# SDCARD.net
KiCad netlist of a schematic drawn in Altium Designer
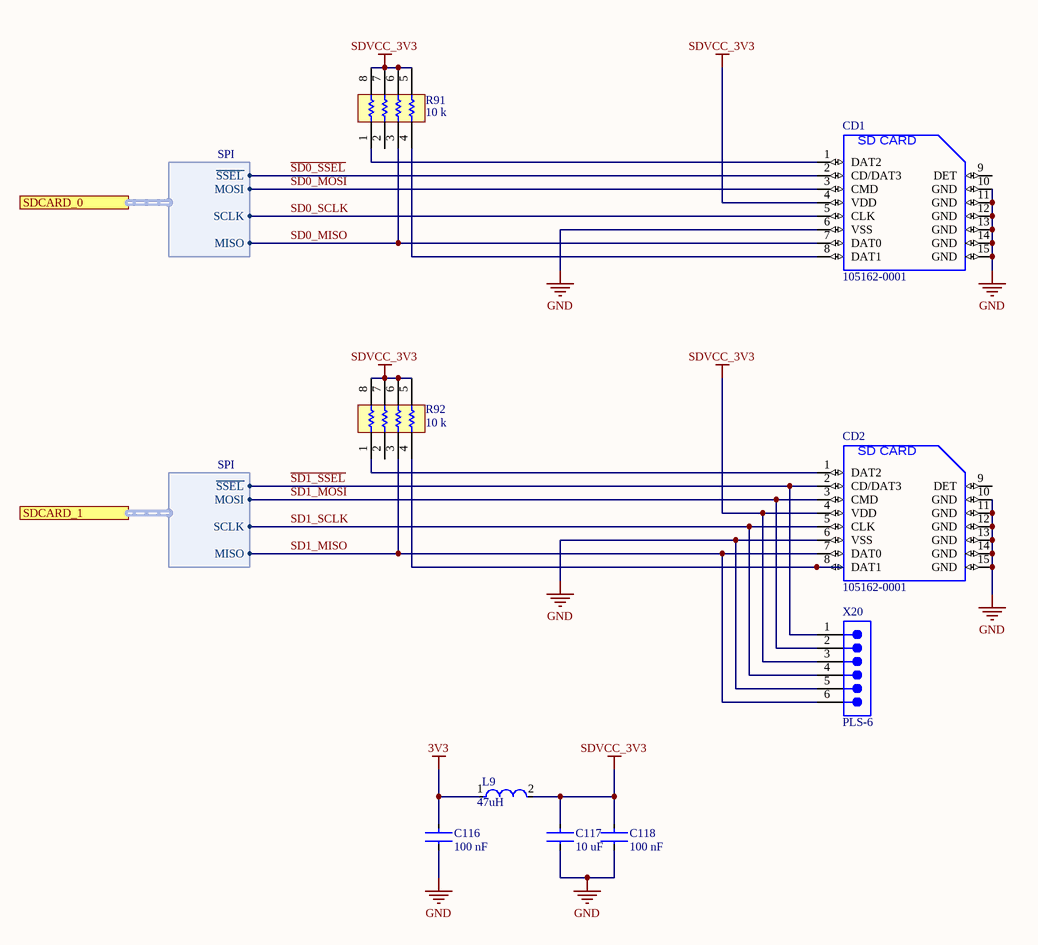
[diagram p0: SDCARD.SchDoc]

(export (version "E")
  (design (tool "Eeschema 10.0.6"))
  (components
    (comp (ref "C116")
      (value "CC0805-1.5pF")
      (footprint "CC0805")
      (description "CL21 Series 0805 1.5pF 50V ±0.25pF Tolerance C0G Multilayer Ceramic Chip Capacitor")
      (fields
        (field (name "MANUFACTURER PART NUMBER") "CL21C1R5CBANNNC")
        (field (name "MANUFACTURER") "Samsung")
        (field (name "CAPACITANCE") "100 nF")
      )
      (libsource (lib "zxevo") (part "CC0805"))
    )
    (comp (ref "C117")
      (value "CC0805-1.5pF")
      (footprint "CC0805")
      (description "CL21 Series 0805 1.5pF 50V ±0.25pF Tolerance C0G Multilayer Ceramic Chip Capacitor")
      (fields
        (field (name "MANUFACTURER PART NUMBER") "CL21C1R5CBANNNC")
        (field (name "MANUFACTURER") "Samsung")
        (field (name "CAPACITANCE") "10 uF")
      )
      (libsource (lib "zxevo") (part "CC0805"))
    )
    (comp (ref "C118")
      (value "CC0805-1.5pF")
      (footprint "CC0805")
      (description "CL21 Series 0805 1.5pF 50V ±0.25pF Tolerance C0G Multilayer Ceramic Chip Capacitor")
      (fields
        (field (name "MANUFACTURER PART NUMBER") "CL21C1R5CBANNNC")
        (field (name "MANUFACTURER") "Samsung")
        (field (name "CAPACITANCE") "100 nF")
      )
      (libsource (lib "zxevo") (part "CC0805"))
    )
    (comp (ref "CD1")
      (value "105162-0001")
      (footprint "105162-0001")
      (description "9 (8 + 1) Position Card Connector microSDâ„¢ Surface Mount, Right Angle Gold")
      (fields (field (name "MF") "Molex"))
      (libsource (lib "zxevo") (part "105162-0001"))
    )
    (comp (ref "CD2")
      (value "105162-0001")
      (footprint "105162-0001")
      (description "9 (8 + 1) Position Card Connector microSDâ„¢ Surface Mount, Right Angle Gold")
      (fields (field (name "MF") "Molex"))
      (libsource (lib "zxevo") (part "105162-0001"))
    )
    (comp (ref "L9")
      (value "NR6028T470M")
      (footprint "FP-NR6028-MFG")
      (description "SMD Power Inductors 47uH ±20% 0.92A 0.39Ω")
      (fields (field (name "INDUCTANCE") "47uH") (field (name "TOLERANCE") "20%"))
      (libsource (lib "Altium Content Vault") (part "725321dda6339637d4d059423bc1c3c"))
    )
    (comp (ref "R91")
      (value "CAY16-103J4LF")
      (footprint "BOUR-CAY16-J4_V")
      (description "Chip Resistor Array, 10 KOhm, +/- 5%, 62.5 mW, -55 to 125 degC, 8-Pin SMD, RoHS, Tape and Reel")
      (fields (field (name "TOLERANCE") "1%") (field (name "RESISTANCE") "10 k"))
      (libsource (lib "Altium Content Vault") (part "RES-P-8"))
    )
    (comp (ref "R92")
      (value "CAY16-103J4LF")
      (footprint "BOUR-CAY16-J4_V")
      (description "Chip Resistor Array, 10 KOhm, +/- 5%, 62.5 mW, -55 to 125 degC, 8-Pin SMD, RoHS, Tape and Reel")
      (fields (field (name "TOLERANCE") "1%") (field (name "RESISTANCE") "10 k"))
      (libsource (lib "Altium Content Vault") (part "RES-P-8"))
    )
    (comp (ref "X20")
      (value "PLS-6")
      (footprint "SMTC-TSW-106-07-X-S")
      (description "0.025\" SQ Post Header, Through-hole, Vertical, -55 to 125 degC, 2.54 mm Pitch, 6-Pin, Male, RoHS")
      (fields (field (name "MANUFACTURER") "Samtec") (field (name "PARTNUMBER") "TSW-106-07-G-S"))
      (libsource (lib "zxevo") (part "PLS-6"))
    )
  )
  (nets
    (net (code "2") (name "/SD0_MISO") (class "Default")
      (node (ref "CD1") (pin "7") (pinfunction "DAT0_7") (pintype "bidirectional"))
      (node (ref "R91") (pin "3") (pinfunction "3_3") (pintype "passive"))
    )
    (net (code "3") (name "/SD0_MOSI") (class "Default")
      (node (ref "CD1") (pin "3") (pinfunction "CMD_3") (pintype "bidirectional"))
    )
    (net (code "4") (name "/SD0_SCLK") (class "Default")
      (node (ref "CD1") (pin "5") (pinfunction "CLK_5") (pintype "bidirectional"))
    )
    (net (code "5") (name "/SD1_MISO") (class "Default")
      (node (ref "CD2") (pin "7") (pinfunction "DAT0_7") (pintype "bidirectional"))
      (node (ref "R92") (pin "3") (pinfunction "3_3") (pintype "passive"))
      (node (ref "X20") (pin "6") (pinfunction "6_6") (pintype "passive"))
    )
    (net (code "6") (name "/SD1_MOSI") (class "Default")
      (node (ref "CD2") (pin "3") (pinfunction "CMD_3") (pintype "bidirectional"))
      (node (ref "X20") (pin "2") (pinfunction "2_2") (pintype "passive"))
    )
    (net (code "7") (name "/SD1_SCLK") (class "Default")
      (node (ref "CD2") (pin "5") (pinfunction "CLK_5") (pintype "bidirectional"))
      (node (ref "X20") (pin "4") (pinfunction "4_4") (pintype "passive"))
    )
    (net (code "9") (name "/~{SD0_SSEL}") (class "Default")
      (node (ref "CD1") (pin "2") (pinfunction "CD/DAT3_2") (pintype "bidirectional"))
    )
    (net (code "10") (name "/~{SD1_SSEL}") (class "Default")
      (node (ref "CD2") (pin "2") (pinfunction "CD/DAT3_2") (pintype "bidirectional"))
      (node (ref "X20") (pin "1") (pinfunction "1_1") (pintype "passive"))
    )
    (net (code "11") (name "3V3") (class "Default")
      (node (ref "C116") (pin "1") (pinfunction "1_1") (pintype "passive"))
      (node (ref "L9") (pin "1") (pinfunction "1_1") (pintype "passive"))
    )
    (net (code "12") (name "GND") (class "Default")
      (node (ref "C116") (pin "2") (pinfunction "2_2") (pintype "passive"))
      (node (ref "C117") (pin "2") (pinfunction "2_2") (pintype "passive"))
      (node (ref "C118") (pin "2") (pinfunction "2_2") (pintype "passive"))
      (node (ref "CD1") (pin "10") (pinfunction "GND_10") (pintype "bidirectional"))
      (node (ref "CD1") (pin "11") (pinfunction "GND_11") (pintype "bidirectional"))
      (node (ref "CD1") (pin "12") (pinfunction "GND_12") (pintype "bidirectional"))
      (node (ref "CD1") (pin "13") (pinfunction "GND_13") (pintype "bidirectional"))
      (node (ref "CD1") (pin "14") (pinfunction "GND_14") (pintype "bidirectional"))
      (node (ref "CD1") (pin "15") (pinfunction "GND_15") (pintype "bidirectional"))
      (node (ref "CD1") (pin "6") (pinfunction "VSS_6") (pintype "bidirectional"))
      (node (ref "CD2") (pin "10") (pinfunction "GND_10") (pintype "bidirectional"))
      (node (ref "CD2") (pin "11") (pinfunction "GND_11") (pintype "bidirectional"))
      (node (ref "CD2") (pin "12") (pinfunction "GND_12") (pintype "bidirectional"))
      (node (ref "CD2") (pin "13") (pinfunction "GND_13") (pintype "bidirectional"))
      (node (ref "CD2") (pin "14") (pinfunction "GND_14") (pintype "bidirectional"))
      (node (ref "CD2") (pin "15") (pinfunction "GND_15") (pintype "bidirectional"))
      (node (ref "CD2") (pin "6") (pinfunction "VSS_6") (pintype "bidirectional"))
      (node (ref "X20") (pin "5") (pinfunction "5_5") (pintype "passive"))
    )
    (net (code "13") (name "Net-(CD1-DAT1)") (class "Default")
      (node (ref "CD1") (pin "8") (pinfunction "DAT1_8") (pintype "bidirectional"))
      (node (ref "R91") (pin "4") (pinfunction "4_4") (pintype "passive"))
    )
    (net (code "14") (name "Net-(CD1-DAT2)") (class "Default")
      (node (ref "CD1") (pin "1") (pinfunction "DAT2_1") (pintype "bidirectional"))
      (node (ref "R91") (pin "1") (pinfunction "1_1") (pintype "passive"))
    )
    (net (code "15") (name "Net-(CD2-DAT1)") (class "Default")
      (node (ref "CD2") (pin "8") (pinfunction "DAT1_8") (pintype "bidirectional"))
      (node (ref "R92") (pin "4") (pinfunction "4_4") (pintype "passive"))
    )
    (net (code "16") (name "Net-(CD2-DAT2)") (class "Default")
      (node (ref "CD2") (pin "1") (pinfunction "DAT2_1") (pintype "bidirectional"))
      (node (ref "R92") (pin "1") (pinfunction "1_1") (pintype "passive"))
    )
    (net (code "17") (name "SDVCC_3V3") (class "Default")
      (node (ref "C117") (pin "1") (pinfunction "1_1") (pintype "passive"))
      (node (ref "C118") (pin "1") (pinfunction "1_1") (pintype "passive"))
      (node (ref "CD1") (pin "4") (pinfunction "VDD_4") (pintype "bidirectional"))
      (node (ref "CD2") (pin "4") (pinfunction "VDD_4") (pintype "bidirectional"))
      (node (ref "L9") (pin "2") (pinfunction "2_2") (pintype "passive"))
      (node (ref "R91") (pin "5") (pinfunction "5_5") (pintype "passive"))
      (node (ref "R91") (pin "6") (pinfunction "6_6") (pintype "passive"))
      (node (ref "R91") (pin "7") (pinfunction "7_7") (pintype "passive"))
      (node (ref "R91") (pin "8") (pinfunction "8_8") (pintype "passive"))
      (node (ref "R92") (pin "5") (pinfunction "5_5") (pintype "passive"))
      (node (ref "R92") (pin "6") (pinfunction "6_6") (pintype "passive"))
      (node (ref "R92") (pin "7") (pinfunction "7_7") (pintype "passive"))
      (node (ref "R92") (pin "8") (pinfunction "8_8") (pintype "passive"))
      (node (ref "X20") (pin "3") (pinfunction "3_3") (pintype "passive"))
    )
    (net (code "18") (name "unconnected-(CD1-DET-Pad9)") (class "Default")
      (node (ref "CD1") (pin "9") (pinfunction "DET_9") (pintype "bidirectional"))
    )
    (net (code "19") (name "unconnected-(CD2-DET-Pad9)") (class "Default")
      (node (ref "CD2") (pin "9") (pinfunction "DET_9") (pintype "bidirectional"))
    )
    (net (code "20") (name "unconnected-(R91-Pad2)") (class "Default")
      (node (ref "R91") (pin "2") (pinfunction "2_2") (pintype "passive"))
    )
    (net (code "21") (name "unconnected-(R92-Pad2)") (class "Default")
      (node (ref "R92") (pin "2") (pinfunction "2_2") (pintype "passive"))
    )
  )
)
